# Sheet3.net
KiCad netlist of a schematic drawn in Altium Designer
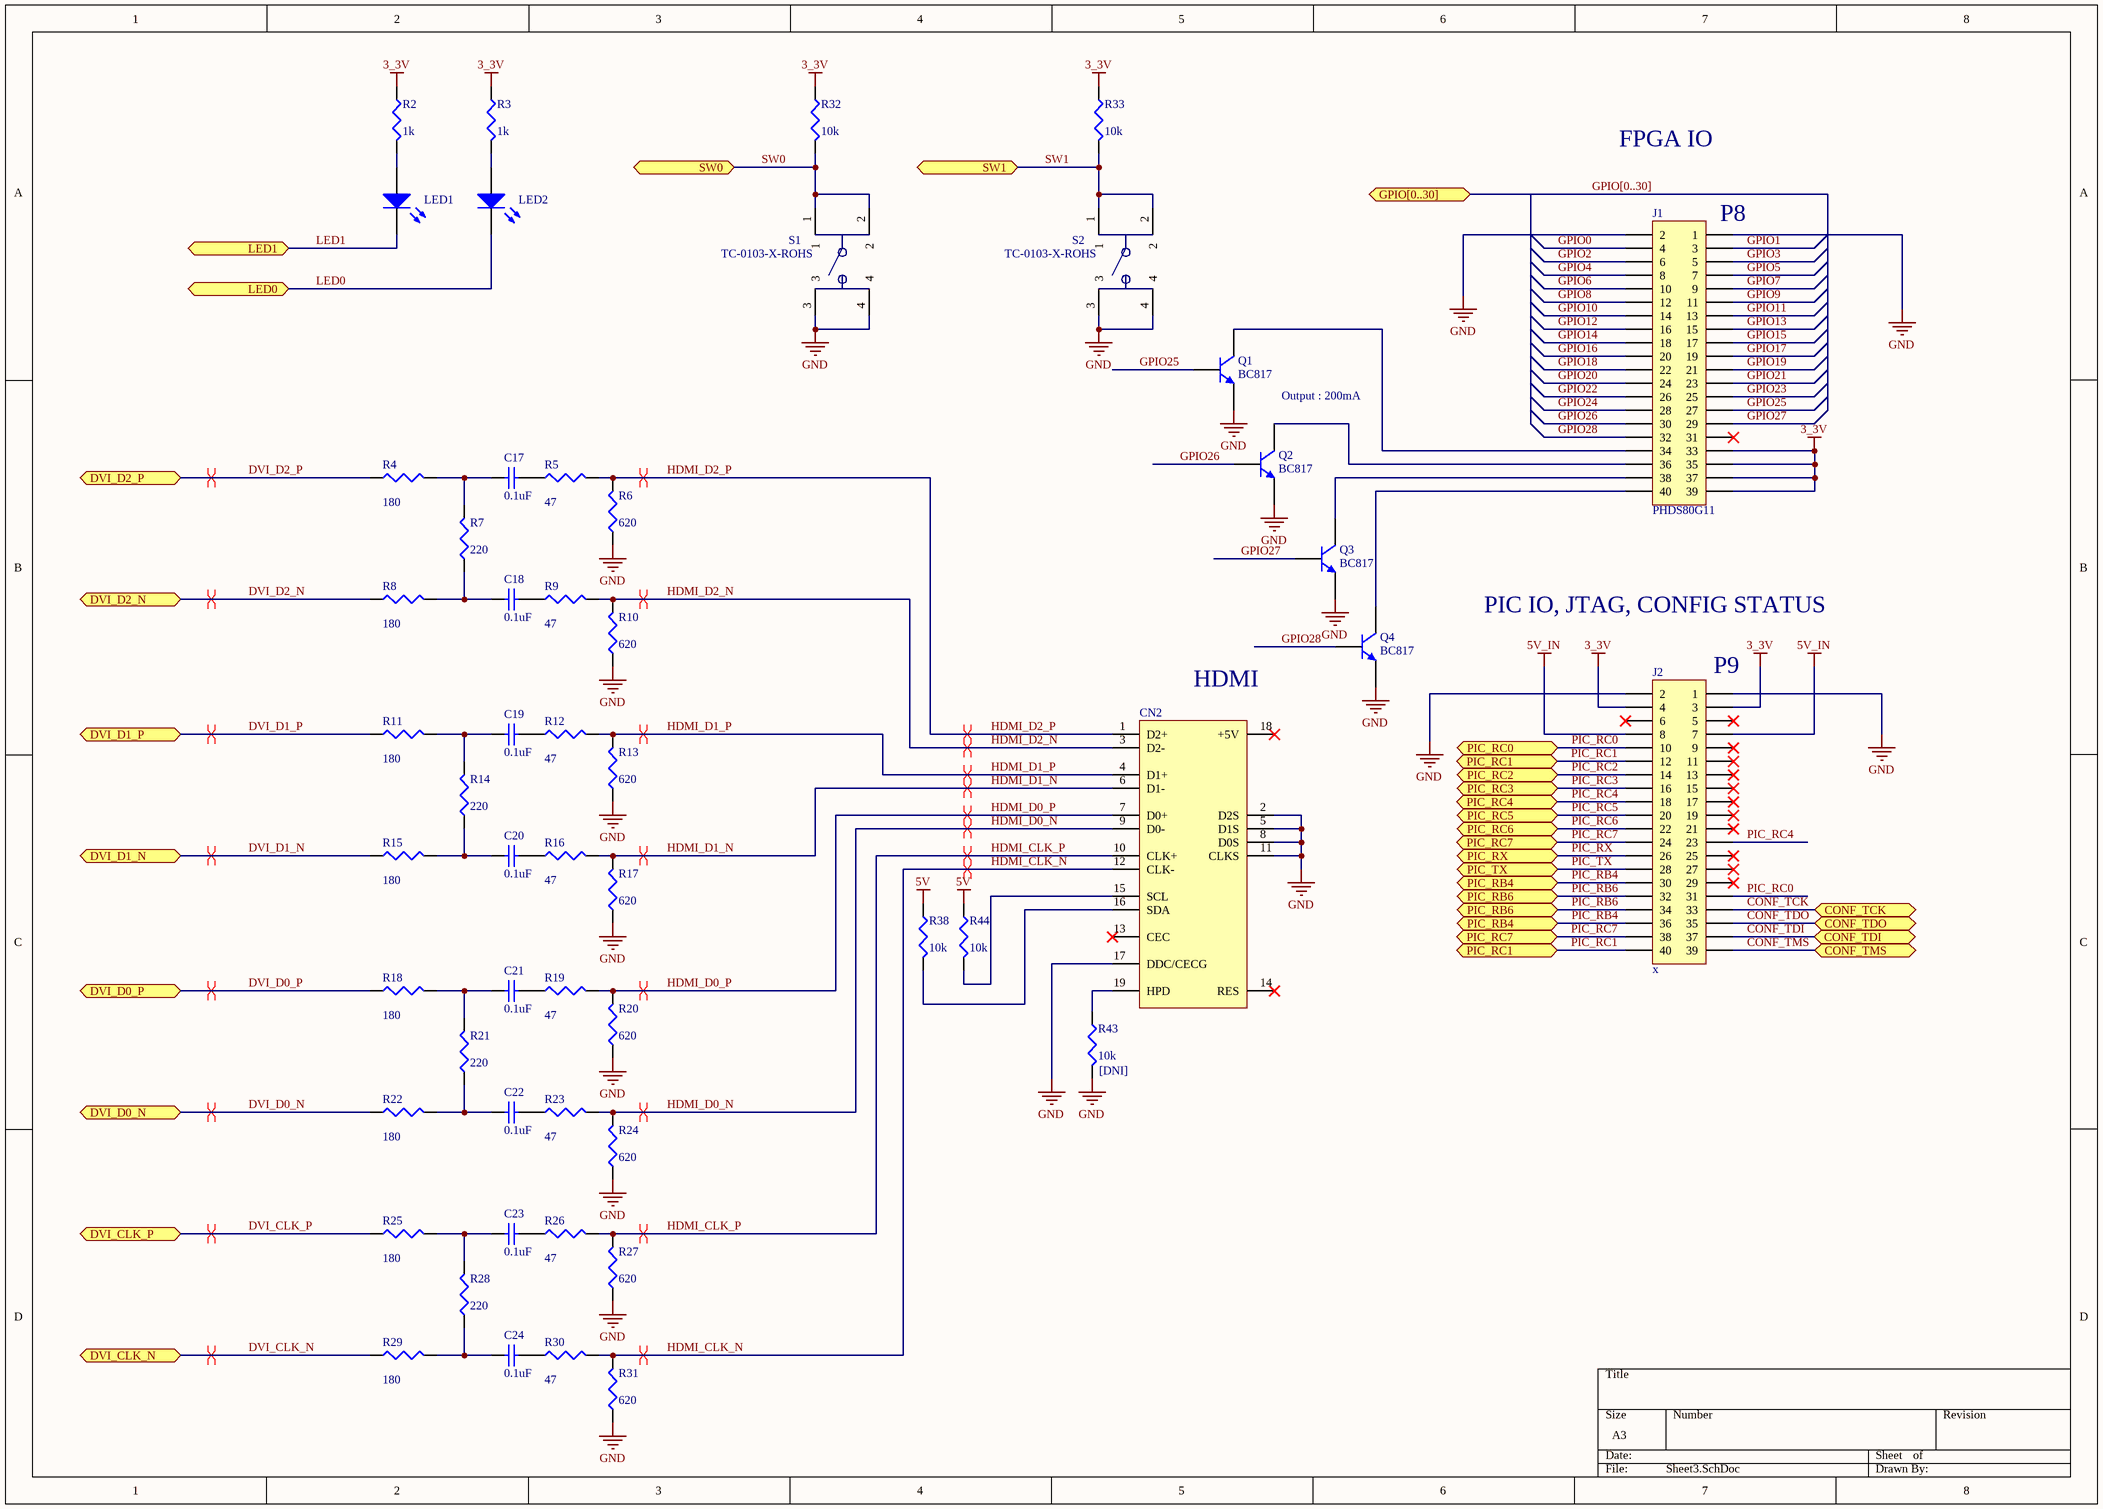
[diagram p0: Sheet3.SchDoc]

(export (version "E")
  (design (tool "Eeschema 10.0.6"))
  (components
    (comp (ref "C17")
      (value "0.1uF")
      (footprint "PcbLib:CHIP1608")
      (description "Capacitor (Semiconductor SIM Model)")
      (fields (field (name "Comment") "MCWR06X000 PTL") (field (name "PUBLISHER") "Altium Limited"))
      (libsource (lib "Miscellaneous Devices") (part "Cap Semi"))
    )
    (comp (ref "C18")
      (value "0.1uF")
      (footprint "PcbLib:CHIP1608")
      (description "Capacitor (Semiconductor SIM Model)")
      (fields (field (name "Comment") "MCWR06X000 PTL") (field (name "PUBLISHER") "Altium Limited"))
      (libsource (lib "Miscellaneous Devices") (part "Cap Semi"))
    )
    (comp (ref "C19")
      (value "0.1uF")
      (footprint "PcbLib:CHIP1608")
      (description "Capacitor (Semiconductor SIM Model)")
      (fields (field (name "Comment") "MCWR06X000 PTL") (field (name "PUBLISHER") "Altium Limited"))
      (libsource (lib "Miscellaneous Devices") (part "Cap Semi"))
    )
    (comp (ref "C20")
      (value "0.1uF")
      (footprint "PcbLib:CHIP1608")
      (description "Capacitor (Semiconductor SIM Model)")
      (fields (field (name "Comment") "MCWR06X000 PTL") (field (name "PUBLISHER") "Altium Limited"))
      (libsource (lib "Miscellaneous Devices") (part "Cap Semi"))
    )
    (comp (ref "C21")
      (value "0.1uF")
      (footprint "PcbLib:CHIP1608")
      (description "Capacitor (Semiconductor SIM Model)")
      (fields (field (name "Comment") "MCWR06X000 PTL") (field (name "PUBLISHER") "Altium Limited"))
      (libsource (lib "Miscellaneous Devices") (part "Cap Semi"))
    )
    (comp (ref "C22")
      (value "0.1uF")
      (footprint "PcbLib:CHIP1608")
      (description "Capacitor (Semiconductor SIM Model)")
      (fields (field (name "Comment") "MCWR06X000 PTL") (field (name "PUBLISHER") "Altium Limited"))
      (libsource (lib "Miscellaneous Devices") (part "Cap Semi"))
    )
    (comp (ref "C23")
      (value "0.1uF")
      (footprint "PcbLib:CHIP1608")
      (description "Capacitor (Semiconductor SIM Model)")
      (fields (field (name "Comment") "MCWR06X000 PTL") (field (name "PUBLISHER") "Altium Limited"))
      (libsource (lib "Miscellaneous Devices") (part "Cap Semi"))
    )
    (comp (ref "C24")
      (value "0.1uF")
      (footprint "PcbLib:CHIP1608")
      (description "Capacitor (Semiconductor SIM Model)")
      (fields (field (name "Comment") "MCWR06X000 PTL") (field (name "PUBLISHER") "Altium Limited"))
      (libsource (lib "Miscellaneous Devices") (part "Cap Semi"))
    )
    (comp (ref "CN2")
      (value "10029449-001RLF")
      (footprint "10029449-001RLF")
      (libsource (lib "Schlib") (part "HDMI_Connector"))
    )
    (comp (ref "J1")
      (value "PHDS80G11")
      (footprint "PcbLib:HDR2X20-Gemini")
      (description "Header, 20-Pin, Dual row")
      (fields (field (name "PUBLISHER") "Altium Limited"))
      (libsource (lib "Miscellaneous Connectors") (part "Header 20X2"))
    )
    (comp (ref "J2")
      (value "x")
      (footprint "PcbLib:HDR2X20-Gemini")
      (description "Header, 20-Pin, Dual row")
      (fields (field (name "PUBLISHER") "Altium Limited"))
      (libsource (lib "Miscellaneous Connectors") (part "Header 20X2"))
    )
    (comp (ref "LED1")
      (value "TO-3216BC-MAE")
      (footprint "PcbLib:LED3216")
      (description "OASISTEK (TO-3216BC-MAE)")
      (fields (field (name "PUBLISHER") "Altium Limited"))
      (libsource (lib "Miscellaneous Devices") (part "LED2"))
    )
    (comp (ref "LED2")
      (value "TO-3216BC-MAE")
      (footprint "PcbLib:LED3216")
      (description "OASISTEK (TO-3216BC-MAE)")
      (fields (field (name "PUBLISHER") "Altium Limited"))
      (libsource (lib "Miscellaneous Devices") (part "LED2"))
    )
    (comp (ref "Q1")
      (value "BC817")
      (footprint "PcbLib:SOT-23")
      (description "NPN General Purpose Amplifier")
      (fields (field (name "PUBLISHER") "Altium Limited"))
      (libsource (lib "Schlib") (part "BC817"))
    )
    (comp (ref "Q2")
      (value "BC817")
      (footprint "PcbLib:SOT-23")
      (description "NPN General Purpose Amplifier")
      (fields (field (name "PUBLISHER") "Altium Limited"))
      (libsource (lib "Schlib") (part "BC817"))
    )
    (comp (ref "Q3")
      (value "BC817")
      (footprint "PcbLib:SOT-23")
      (description "NPN General Purpose Amplifier")
      (fields (field (name "PUBLISHER") "Altium Limited"))
      (libsource (lib "Schlib") (part "BC817"))
    )
    (comp (ref "Q4")
      (value "BC817")
      (footprint "PcbLib:SOT-23")
      (description "NPN General Purpose Amplifier")
      (fields (field (name "PUBLISHER") "Altium Limited"))
      (libsource (lib "Schlib") (part "BC817"))
    )
    (comp (ref "R2")
      (value "1k")
      (footprint "PcbLib:CHIP1608")
      (description "Resistor")
      (fields (field (name "Comment") "MCMR06X1001FTL") (field (name "PUBLISHER") "Altium Limited"))
      (libsource (lib "Miscellaneous Devices") (part "Res3"))
    )
    (comp (ref "R3")
      (value "1k")
      (footprint "PcbLib:CHIP1608")
      (description "Resistor")
      (fields (field (name "Comment") "MCMR06X1001FTL") (field (name "PUBLISHER") "Altium Limited"))
      (libsource (lib "Miscellaneous Devices") (part "Res3"))
    )
    (comp (ref "R4")
      (value "180")
      (footprint "PcbLib:CHIP1608")
      (description "Resistor")
      (fields (field (name "Comment") "MC0063W06031270R") (field (name "PUBLISHER") "Altium Limited"))
      (libsource (lib "Miscellaneous Devices") (part "Res3"))
    )
    (comp (ref "R5")
      (value "47")
      (footprint "PcbLib:CHIP1608")
      (description "Resistor")
      (fields (field (name "Comment") "MCWR06X000 PTL") (field (name "PUBLISHER") "Altium Limited"))
      (libsource (lib "Miscellaneous Devices") (part "Res3"))
    )
    (comp (ref "R6")
      (value "620")
      (footprint "PcbLib:CHIP1608")
      (description "Resistor")
      (fields (field (name "Comment") "MCMR06X1001FTL") (field (name "PUBLISHER") "Altium Limited"))
      (libsource (lib "Miscellaneous Devices") (part "Res3"))
    )
    (comp (ref "R7")
      (value "220")
      (footprint "PcbLib:CHIP1608")
      (description "Resistor")
      (fields (field (name "Comment") "MCMR06X1001FTL") (field (name "PUBLISHER") "Altium Limited"))
      (libsource (lib "Miscellaneous Devices") (part "Res3"))
    )
    (comp (ref "R8")
      (value "180")
      (footprint "PcbLib:CHIP1608")
      (description "Resistor")
      (fields (field (name "Comment") "MC0063W06031270R") (field (name "PUBLISHER") "Altium Limited"))
      (libsource (lib "Miscellaneous Devices") (part "Res3"))
    )
    (comp (ref "R9")
      (value "47")
      (footprint "PcbLib:CHIP1608")
      (description "Resistor")
      (fields (field (name "Comment") "MCWR06X000 PTL") (field (name "PUBLISHER") "Altium Limited"))
      (libsource (lib "Miscellaneous Devices") (part "Res3"))
    )
    (comp (ref "R10")
      (value "620")
      (footprint "PcbLib:CHIP1608")
      (description "Resistor")
      (fields (field (name "Comment") "MCMR06X1001FTL") (field (name "PUBLISHER") "Altium Limited"))
      (libsource (lib "Miscellaneous Devices") (part "Res3"))
    )
    (comp (ref "R11")
      (value "180")
      (footprint "PcbLib:CHIP1608")
      (description "Resistor")
      (fields (field (name "Comment") "MC0063W06031270R") (field (name "PUBLISHER") "Altium Limited"))
      (libsource (lib "Miscellaneous Devices") (part "Res3"))
    )
    (comp (ref "R12")
      (value "47")
      (footprint "PcbLib:CHIP1608")
      (description "Resistor")
      (fields (field (name "Comment") "MCWR06X000 PTL") (field (name "PUBLISHER") "Altium Limited"))
      (libsource (lib "Miscellaneous Devices") (part "Res3"))
    )
    (comp (ref "R13")
      (value "620")
      (footprint "PcbLib:CHIP1608")
      (description "Resistor")
      (fields (field (name "Comment") "MCMR06X1001FTL") (field (name "PUBLISHER") "Altium Limited"))
      (libsource (lib "Miscellaneous Devices") (part "Res3"))
    )
    (comp (ref "R14")
      (value "220")
      (footprint "PcbLib:CHIP1608")
      (description "Resistor")
      (fields (field (name "Comment") "MCMR06X1001FTL") (field (name "PUBLISHER") "Altium Limited"))
      (libsource (lib "Miscellaneous Devices") (part "Res3"))
    )
    (comp (ref "R15")
      (value "180")
      (footprint "PcbLib:CHIP1608")
      (description "Resistor")
      (fields (field (name "Comment") "MC0063W06031270R") (field (name "PUBLISHER") "Altium Limited"))
      (libsource (lib "Miscellaneous Devices") (part "Res3"))
    )
    (comp (ref "R16")
      (value "47")
      (footprint "PcbLib:CHIP1608")
      (description "Resistor")
      (fields (field (name "Comment") "MCWR06X000 PTL") (field (name "PUBLISHER") "Altium Limited"))
      (libsource (lib "Miscellaneous Devices") (part "Res3"))
    )
    (comp (ref "R17")
      (value "620")
      (footprint "PcbLib:CHIP1608")
      (description "Resistor")
      (fields (field (name "Comment") "MCMR06X1001FTL") (field (name "PUBLISHER") "Altium Limited"))
      (libsource (lib "Miscellaneous Devices") (part "Res3"))
    )
    (comp (ref "R18")
      (value "180")
      (footprint "PcbLib:CHIP1608")
      (description "Resistor")
      (fields (field (name "Comment") "MC0063W06031270R") (field (name "PUBLISHER") "Altium Limited"))
      (libsource (lib "Miscellaneous Devices") (part "Res3"))
    )
    (comp (ref "R19")
      (value "47")
      (footprint "PcbLib:CHIP1608")
      (description "Resistor")
      (fields (field (name "Comment") "MCWR06X000 PTL") (field (name "PUBLISHER") "Altium Limited"))
      (libsource (lib "Miscellaneous Devices") (part "Res3"))
    )
    (comp (ref "R20")
      (value "620")
      (footprint "PcbLib:CHIP1608")
      (description "Resistor")
      (fields (field (name "Comment") "MCMR06X1001FTL") (field (name "PUBLISHER") "Altium Limited"))
      (libsource (lib "Miscellaneous Devices") (part "Res3"))
    )
    (comp (ref "R21")
      (value "220")
      (footprint "PcbLib:CHIP1608")
      (description "Resistor")
      (fields (field (name "Comment") "MCMR06X1001FTL") (field (name "PUBLISHER") "Altium Limited"))
      (libsource (lib "Miscellaneous Devices") (part "Res3"))
    )
    (comp (ref "R22")
      (value "180")
      (footprint "PcbLib:CHIP1608")
      (description "Resistor")
      (fields (field (name "Comment") "MC0063W06031270R") (field (name "PUBLISHER") "Altium Limited"))
      (libsource (lib "Miscellaneous Devices") (part "Res3"))
    )
    (comp (ref "R23")
      (value "47")
      (footprint "PcbLib:CHIP1608")
      (description "Resistor")
      (fields (field (name "Comment") "MCWR06X000 PTL") (field (name "PUBLISHER") "Altium Limited"))
      (libsource (lib "Miscellaneous Devices") (part "Res3"))
    )
    (comp (ref "R24")
      (value "620")
      (footprint "PcbLib:CHIP1608")
      (description "Resistor")
      (fields (field (name "Comment") "MCMR06X1001FTL") (field (name "PUBLISHER") "Altium Limited"))
      (libsource (lib "Miscellaneous Devices") (part "Res3"))
    )
    (comp (ref "R25")
      (value "180")
      (footprint "PcbLib:CHIP1608")
      (description "Resistor")
      (fields (field (name "Comment") "MC0063W06031270R") (field (name "PUBLISHER") "Altium Limited"))
      (libsource (lib "Miscellaneous Devices") (part "Res3"))
    )
    (comp (ref "R26")
      (value "47")
      (footprint "PcbLib:CHIP1608")
      (description "Resistor")
      (fields (field (name "Comment") "MCWR06X000 PTL") (field (name "PUBLISHER") "Altium Limited"))
      (libsource (lib "Miscellaneous Devices") (part "Res3"))
    )
    (comp (ref "R27")
      (value "620")
      (footprint "PcbLib:CHIP1608")
      (description "Resistor")
      (fields (field (name "Comment") "MCMR06X1001FTL") (field (name "PUBLISHER") "Altium Limited"))
      (libsource (lib "Miscellaneous Devices") (part "Res3"))
    )
    (comp (ref "R28")
      (value "220")
      (footprint "PcbLib:CHIP1608")
      (description "Resistor")
      (fields (field (name "Comment") "MCMR06X1001FTL") (field (name "PUBLISHER") "Altium Limited"))
      (libsource (lib "Miscellaneous Devices") (part "Res3"))
    )
    (comp (ref "R29")
      (value "180")
      (footprint "PcbLib:CHIP1608")
      (description "Resistor")
      (fields (field (name "Comment") "MC0063W06031270R") (field (name "PUBLISHER") "Altium Limited"))
      (libsource (lib "Miscellaneous Devices") (part "Res3"))
    )
    (comp (ref "R30")
      (value "47")
      (footprint "PcbLib:CHIP1608")
      (description "Resistor")
      (fields (field (name "Comment") "MCWR06X000 PTL") (field (name "PUBLISHER") "Altium Limited"))
      (libsource (lib "Miscellaneous Devices") (part "Res3"))
    )
    (comp (ref "R31")
      (value "620")
      (footprint "PcbLib:CHIP1608")
      (description "Resistor")
      (fields (field (name "Comment") "MCMR06X1001FTL") (field (name "PUBLISHER") "Altium Limited"))
      (libsource (lib "Miscellaneous Devices") (part "Res3"))
    )
    (comp (ref "R32")
      (value "10k")
      (footprint "PcbLib:CHIP1608")
      (description "Resistor")
      (fields (field (name "Comment") "MCWR06X1002FTL") (field (name "PUBLISHER") "Altium Limited"))
      (libsource (lib "Miscellaneous Devices") (part "Res3"))
    )
    (comp (ref "R33")
      (value "10k")
      (footprint "PcbLib:CHIP1608")
      (description "Resistor")
      (fields (field (name "Comment") "MCWR06X1002FTL") (field (name "PUBLISHER") "Altium Limited"))
      (libsource (lib "Miscellaneous Devices") (part "Res3"))
    )
    (comp (ref "R38")
      (value "10k")
      (footprint "PcbLib:CHIP1608")
      (description "Resistor")
      (fields (field (name "Comment") "MCWR06X1002FTL") (field (name "PUBLISHER") "Altium Limited"))
      (libsource (lib "Miscellaneous Devices") (part "Res3"))
    )
    (comp (ref "R43")
      (value "10k")
      (footprint "PcbLib:CHIP1608")
      (description "Resistor")
      (fields
        (field (name "ASSEMBLY") "[DNI]")
        (field (name "Comment") "MCWR06X1002FTL")
        (field (name "PUBLISHER") "Altium Limited")
      )
      (libsource (lib "Miscellaneous Devices") (part "Res3"))
    )
    (comp (ref "R44")
      (value "10k")
      (footprint "PcbLib:CHIP1608")
      (description "Resistor")
      (fields (field (name "Comment") "MCWR06X1002FTL") (field (name "PUBLISHER") "Altium Limited"))
      (libsource (lib "Miscellaneous Devices") (part "Res3"))
    )
    (comp (ref "S1")
      (value "TC-0103-X-ROHS")
      (footprint "TACK_SW 6x6mm")
      (description "WEALTH METAL")
      (libsource (lib "Schlib1") (part "TC-0103-X-ROHS"))
    )
    (comp (ref "S2")
      (value "TC-0103-X-ROHS")
      (footprint "TACK_SW 6x6mm")
      (description "WEALTH METAL")
      (libsource (lib "Schlib1") (part "TC-0103-X-ROHS"))
    )
  )
  (nets
    (net (code "3") (name "/CONF_TCK") (class "Default")
      (node (ref "J2") (pin "33") (pinfunction "33_33") (pintype "passive"))
    )
    (net (code "4") (name "/CONF_TDI") (class "Default")
      (node (ref "J2") (pin "37") (pinfunction "37_37") (pintype "passive"))
    )
    (net (code "5") (name "/CONF_TDO") (class "Default")
      (node (ref "J2") (pin "35") (pinfunction "35_35") (pintype "passive"))
    )
    (net (code "6") (name "/CONF_TMS") (class "Default")
      (node (ref "J2") (pin "39") (pinfunction "39_39") (pintype "passive"))
    )
    (net (code "7") (name "/DVI_CLK_N") (class "Default")
      (node (ref "R29") (pin "1") (pinfunction "1_1") (pintype "passive"))
    )
    (net (code "8") (name "/DVI_CLK_P") (class "Default")
      (node (ref "R25") (pin "1") (pinfunction "1_1") (pintype "passive"))
    )
    (net (code "9") (name "/DVI_D0_N") (class "Default")
      (node (ref "R22") (pin "1") (pinfunction "1_1") (pintype "passive"))
    )
    (net (code "10") (name "/DVI_D0_P") (class "Default")
      (node (ref "R18") (pin "1") (pinfunction "1_1") (pintype "passive"))
    )
    (net (code "11") (name "/DVI_D1_N") (class "Default")
      (node (ref "R15") (pin "1") (pinfunction "1_1") (pintype "passive"))
    )
    (net (code "12") (name "/DVI_D1_P") (class "Default")
      (node (ref "R11") (pin "1") (pinfunction "1_1") (pintype "passive"))
    )
    (net (code "13") (name "/DVI_D2_N") (class "Default")
      (node (ref "R8") (pin "1") (pinfunction "1_1") (pintype "passive"))
    )
    (net (code "14") (name "/DVI_D2_P") (class "Default")
      (node (ref "R4") (pin "1") (pinfunction "1_1") (pintype "passive"))
    )
    (net (code "15") (name "/GPIO0") (class "Default")
      (node (ref "J1") (pin "4") (pinfunction "4_4") (pintype "passive"))
    )
    (net (code "16") (name "/GPIO1") (class "Default")
      (node (ref "J1") (pin "3") (pinfunction "3_3") (pintype "passive"))
    )
    (net (code "17") (name "/GPIO2") (class "Default")
      (node (ref "J1") (pin "6") (pinfunction "6_6") (pintype "passive"))
    )
    (net (code "18") (name "/GPIO3") (class "Default")
      (node (ref "J1") (pin "5") (pinfunction "5_5") (pintype "passive"))
    )
    (net (code "19") (name "/GPIO4") (class "Default")
      (node (ref "J1") (pin "8") (pinfunction "8_8") (pintype "passive"))
    )
    (net (code "20") (name "/GPIO5") (class "Default")
      (node (ref "J1") (pin "7") (pinfunction "7_7") (pintype "passive"))
    )
    (net (code "21") (name "/GPIO6") (class "Default")
      (node (ref "J1") (pin "10") (pinfunction "10_10") (pintype "passive"))
    )
    (net (code "22") (name "/GPIO7") (class "Default")
      (node (ref "J1") (pin "9") (pinfunction "9_9") (pintype "passive"))
    )
    (net (code "23") (name "/GPIO8") (class "Default")
      (node (ref "J1") (pin "12") (pinfunction "12_12") (pintype "passive"))
    )
    (net (code "24") (name "/GPIO9") (class "Default")
      (node (ref "J1") (pin "11") (pinfunction "11_11") (pintype "passive"))
    )
    (net (code "25") (name "/GPIO10") (class "Default")
      (node (ref "J1") (pin "14") (pinfunction "14_14") (pintype "passive"))
    )
    (net (code "26") (name "/GPIO11") (class "Default")
      (node (ref "J1") (pin "13") (pinfunction "13_13") (pintype "passive"))
    )
    (net (code "27") (name "/GPIO12") (class "Default")
      (node (ref "J1") (pin "16") (pinfunction "16_16") (pintype "passive"))
    )
    (net (code "28") (name "/GPIO13") (class "Default")
      (node (ref "J1") (pin "15") (pinfunction "15_15") (pintype "passive"))
    )
    (net (code "29") (name "/GPIO14") (class "Default")
      (node (ref "J1") (pin "18") (pinfunction "18_18") (pintype "passive"))
    )
    (net (code "30") (name "/GPIO15") (class "Default")
      (node (ref "J1") (pin "17") (pinfunction "17_17") (pintype "passive"))
    )
    (net (code "31") (name "/GPIO16") (class "Default")
      (node (ref "J1") (pin "20") (pinfunction "20_20") (pintype "passive"))
    )
    (net (code "32") (name "/GPIO17") (class "Default")
      (node (ref "J1") (pin "19") (pinfunction "19_19") (pintype "passive"))
    )
    (net (code "33") (name "/GPIO18") (class "Default")
      (node (ref "J1") (pin "22") (pinfunction "22_22") (pintype "passive"))
    )
    (net (code "34") (name "/GPIO19") (class "Default")
      (node (ref "J1") (pin "21") (pinfunction "21_21") (pintype "passive"))
    )
    (net (code "35") (name "/GPIO20") (class "Default")
      (node (ref "J1") (pin "24") (pinfunction "24_24") (pintype "passive"))
    )
    (net (code "36") (name "/GPIO21") (class "Default")
      (node (ref "J1") (pin "23") (pinfunction "23_23") (pintype "passive"))
    )
    (net (code "37") (name "/GPIO22") (class "Default")
      (node (ref "J1") (pin "26") (pinfunction "26_26") (pintype "passive"))
    )
    (net (code "38") (name "/GPIO23") (class "Default")
      (node (ref "J1") (pin "25") (pinfunction "25_25") (pintype "passive"))
    )
    (net (code "39") (name "/GPIO24") (class "Default")
      (node (ref "J1") (pin "28") (pinfunction "28_28") (pintype "passive"))
    )
    (net (code "40") (name "/GPIO25") (class "Default")
      (node (ref "J1") (pin "27") (pinfunction "27_27") (pintype "passive"))
      (node (ref "Q1") (pin "1") (pinfunction "B_1") (pintype "passive"))
    )
    (net (code "41") (name "/GPIO26") (class "Default")
      (node (ref "J1") (pin "30") (pinfunction "30_30") (pintype "passive"))
      (node (ref "Q2") (pin "1") (pinfunction "B_1") (pintype "passive"))
    )
    (net (code "42") (name "/GPIO27") (class "Default")
      (node (ref "J1") (pin "29") (pinfunction "29_29") (pintype "passive"))
      (node (ref "Q3") (pin "1") (pinfunction "B_1") (pintype "passive"))
    )
    (net (code "43") (name "/GPIO28") (class "Default")
      (node (ref "J1") (pin "32") (pinfunction "32_32") (pintype "passive"))
      (node (ref "Q4") (pin "1") (pinfunction "B_1") (pintype "passive"))
    )
    (net (code "45") (name "/HDMI_CLK_N") (class "Default")
      (node (ref "CN2") (pin "12") (pinfunction "CLK-_12") (pintype "passive"))
      (node (ref "R30") (pin "2") (pinfunction "2_2") (pintype "passive"))
      (node (ref "R31") (pin "2") (pinfunction "2_2") (pintype "passive"))
    )
    (net (code "46") (name "/HDMI_CLK_P") (class "Default")
      (node (ref "CN2") (pin "10") (pinfunction "CLK+_10") (pintype "passive"))
      (node (ref "R26") (pin "2") (pinfunction "2_2") (pintype "passive"))
      (node (ref "R27") (pin "2") (pinfunction "2_2") (pintype "passive"))
    )
    (net (code "47") (name "/HDMI_D0_N") (class "Default")
      (node (ref "CN2") (pin "9") (pinfunction "D0-_9") (pintype "passive"))
      (node (ref "R23") (pin "2") (pinfunction "2_2") (pintype "passive"))
      (node (ref "R24") (pin "2") (pinfunction "2_2") (pintype "passive"))
    )
    (net (code "48") (name "/HDMI_D0_P") (class "Default")
      (node (ref "CN2") (pin "7") (pinfunction "D0+_7") (pintype "passive"))
      (node (ref "R19") (pin "2") (pinfunction "2_2") (pintype "passive"))
      (node (ref "R20") (pin "2") (pinfunction "2_2") (pintype "passive"))
    )
    (net (code "49") (name "/HDMI_D1_N") (class "Default")
      (node (ref "CN2") (pin "6") (pinfunction "D1-_6") (pintype "passive"))
      (node (ref "R16") (pin "2") (pinfunction "2_2") (pintype "passive"))
      (node (ref "R17") (pin "2") (pinfunction "2_2") (pintype "passive"))
    )
    (net (code "50") (name "/HDMI_D1_P") (class "Default")
      (node (ref "CN2") (pin "4") (pinfunction "D1+_4") (pintype "passive"))
      (node (ref "R12") (pin "2") (pinfunction "2_2") (pintype "passive"))
      (node (ref "R13") (pin "2") (pinfunction "2_2") (pintype "passive"))
    )
    (net (code "51") (name "/HDMI_D2_N") (class "Default")
      (node (ref "CN2") (pin "3") (pinfunction "D2-_3") (pintype "passive"))
      (node (ref "R10") (pin "2") (pinfunction "2_2") (pintype "passive"))
      (node (ref "R9") (pin "2") (pinfunction "2_2") (pintype "passive"))
    )
    (net (code "52") (name "/HDMI_D2_P") (class "Default")
      (node (ref "CN2") (pin "1") (pinfunction "D2+_1") (pintype "passive"))
      (node (ref "R5") (pin "2") (pinfunction "2_2") (pintype "passive"))
      (node (ref "R6") (pin "2") (pinfunction "2_2") (pintype "passive"))
    )
    (net (code "53") (name "/LED0") (class "Default")
      (node (ref "LED2") (pin "2") (pinfunction "K_2") (pintype "passive"))
    )
    (net (code "54") (name "/LED1") (class "Default")
      (node (ref "LED1") (pin "2") (pinfunction "K_2") (pintype "passive"))
    )
    (net (code "55") (name "/PIC_RB4") (class "Default")
      (node (ref "J2") (pin "30") (pinfunction "30_30") (pintype "passive"))
      (node (ref "J2") (pin "36") (pinfunction "36_36") (pintype "passive"))
    )
    (net (code "56") (name "/PIC_RB6") (class "Default")
      (node (ref "J2") (pin "32") (pinfunction "32_32") (pintype "passive"))
      (node (ref "J2") (pin "34") (pinfunction "34_34") (pintype "passive"))
    )
    (net (code "57") (name "/PIC_RC0") (class "Default")
      (node (ref "J2") (pin "10") (pinfunction "10_10") (pintype "passive"))
      (node (ref "J2") (pin "31") (pinfunction "31_31") (pintype "passive"))
    )
    (net (code "58") (name "/PIC_RC1") (class "Default")
      (node (ref "J2") (pin "12") (pinfunction "12_12") (pintype "passive"))
      (node (ref "J2") (pin "40") (pinfunction "40_40") (pintype "passive"))
    )
    (net (code "59") (name "/PIC_RC2") (class "Default")
      (node (ref "J2") (pin "14") (pinfunction "14_14") (pintype "passive"))
    )
    (net (code "60") (name "/PIC_RC3") (class "Default")
      (node (ref "J2") (pin "16") (pinfunction "16_16") (pintype "passive"))
    )
    (net (code "61") (name "/PIC_RC4") (class "Default")
      (node (ref "J2") (pin "18") (pinfunction "18_18") (pintype "passive"))
      (node (ref "J2") (pin "23") (pinfunction "23_23") (pintype "passive"))
    )
    (net (code "62") (name "/PIC_RC5") (class "Default")
      (node (ref "J2") (pin "20") (pinfunction "20_20") (pintype "passive"))
    )
    (net (code "63") (name "/PIC_RC6") (class "Default")
      (node (ref "J2") (pin "22") (pinfunction "22_22") (pintype "passive"))
    )
    (net (code "64") (name "/PIC_RC7") (class "Default")
      (node (ref "J2") (pin "24") (pinfunction "24_24") (pintype "passive"))
      (node (ref "J2") (pin "38") (pinfunction "38_38") (pintype "passive"))
    )
    (net (code "65") (name "/PIC_RX") (class "Default")
      (node (ref "J2") (pin "26") (pinfunction "26_26") (pintype "passive"))
    )
    (net (code "66") (name "/PIC_TX") (class "Default")
      (node (ref "J2") (pin "28") (pinfunction "28_28") (pintype "passive"))
    )
    (net (code "67") (name "/SW0") (class "Default")
      (node (ref "R32") (pin "2") (pinfunction "2_2") (pintype "passive"))
      (node (ref "S1") (pin "1") (pinfunction "1_1") (pintype "passive"))
      (node (ref "S1") (pin "2") (pinfunction "2_2") (pintype "passive"))
    )
    (net (code "68") (name "/SW1") (class "Default")
      (node (ref "R33") (pin "2") (pinfunction "2_2") (pintype "passive"))
      (node (ref "S2") (pin "1") (pinfunction "1_1") (pintype "passive"))
      (node (ref "S2") (pin "2") (pinfunction "2_2") (pintype "passive"))
    )
    (net (code "69") (name "3_3V") (class "Default")
      (node (ref "J1") (pin "33") (pinfunction "33_33") (pintype "passive"))
      (node (ref "J1") (pin "35") (pinfunction "35_35") (pintype "passive"))
      (node (ref "J1") (pin "37") (pinfunction "37_37") (pintype "passive"))
      (node (ref "J1") (pin "39") (pinfunction "39_39") (pintype "passive"))
      (node (ref "J2") (pin "3") (pinfunction "3_3") (pintype "passive"))
      (node (ref "J2") (pin "4") (pinfunction "4_4") (pintype "passive"))
      (node (ref "R2") (pin "1") (pinfunction "1_1") (pintype "passive"))
      (node (ref "R3") (pin "1") (pinfunction "1_1") (pintype "passive"))
      (node (ref "R32") (pin "1") (pinfunction "1_1") (pintype "passive"))
      (node (ref "R33") (pin "1") (pinfunction "1_1") (pintype "passive"))
    )
    (net (code "70") (name "5V") (class "Default")
      (node (ref "R38") (pin "1") (pinfunction "1_1") (pintype "passive"))
      (node (ref "R44") (pin "1") (pinfunction "1_1") (pintype "passive"))
    )
    (net (code "71") (name "5V_IN") (class "Default")
      (node (ref "J2") (pin "7") (pinfunction "7_7") (pintype "passive"))
      (node (ref "J2") (pin "8") (pinfunction "8_8") (pintype "passive"))
    )
    (net (code "72") (name "GND") (class "Default")
      (node (ref "CN2") (pin "11") (pinfunction "CLKS_11") (pintype "passive"))
      (node (ref "CN2") (pin "17") (pinfunction "DDC/CECG_17") (pintype "passive"))
      (node (ref "CN2") (pin "2") (pinfunction "D2S_2") (pintype "passive"))
      (node (ref "CN2") (pin "5") (pinfunction "D1S_5") (pintype "passive"))
      (node (ref "CN2") (pin "8") (pinfunction "D0S_8") (pintype "passive"))
      (node (ref "J1") (pin "1") (pinfunction "1_1") (pintype "passive"))
      (node (ref "J1") (pin "2") (pinfunction "2_2") (pintype "passive"))
      (node (ref "J2") (pin "1") (pinfunction "1_1") (pintype "passive"))
      (node (ref "J2") (pin "2") (pinfunction "2_2") (pintype "passive"))
      (node (ref "Q1") (pin "2") (pinfunction "E_2") (pintype "passive"))
      (node (ref "Q2") (pin "2") (pinfunction "E_2") (pintype "passive"))
      (node (ref "Q3") (pin "2") (pinfunction "E_2") (pintype "passive"))
      (node (ref "Q4") (pin "2") (pinfunction "E_2") (pintype "passive"))
      (node (ref "R10") (pin "1") (pinfunction "1_1") (pintype "passive"))
      (node (ref "R13") (pin "1") (pinfunction "1_1") (pintype "passive"))
      (node (ref "R17") (pin "1") (pinfunction "1_1") (pintype "passive"))
      (node (ref "R20") (pin "1") (pinfunction "1_1") (pintype "passive"))
      (node (ref "R24") (pin "1") (pinfunction "1_1") (pintype "passive"))
      (node (ref "R27") (pin "1") (pinfunction "1_1") (pintype "passive"))
      (node (ref "R31") (pin "1") (pinfunction "1_1") (pintype "passive"))
      (node (ref "R43") (pin "2") (pinfunction "2_2") (pintype "passive"))
      (node (ref "R6") (pin "1") (pinfunction "1_1") (pintype "passive"))
      (node (ref "S1") (pin "3") (pinfunction "3_3") (pintype "passive"))
      (node (ref "S1") (pin "4") (pinfunction "4_4") (pintype "passive"))
      (node (ref "S2") (pin "3") (pinfunction "3_3") (pintype "passive"))
      (node (ref "S2") (pin "4") (pinfunction "4_4") (pintype "passive"))
    )
    (net (code "73") (name "Net-(C17-Pad1)") (class "Default")
      (node (ref "C17") (pin "1") (pinfunction "1_1") (pintype "passive"))
      (node (ref "R5") (pin "1") (pinfunction "1_1") (pintype "passive"))
    )
    (net (code "74") (name "Net-(C17-Pad2)") (class "Default")
      (node (ref "C17") (pin "2") (pinfunction "2_2") (pintype "passive"))
      (node (ref "R4") (pin "2") (pinfunction "2_2") (pintype "passive"))
      (node (ref "R7") (pin "2") (pinfunction "2_2") (pintype "passive"))
    )
    (net (code "75") (name "Net-(C18-Pad1)") (class "Default")
      (node (ref "C18") (pin "1") (pinfunction "1_1") (pintype "passive"))
      (node (ref "R9") (pin "1") (pinfunction "1_1") (pintype "passive"))
    )
    (net (code "76") (name "Net-(C18-Pad2)") (class "Default")
      (node (ref "C18") (pin "2") (pinfunction "2_2") (pintype "passive"))
      (node (ref "R7") (pin "1") (pinfunction "1_1") (pintype "passive"))
      (node (ref "R8") (pin "2") (pinfunction "2_2") (pintype "passive"))
    )
    (net (code "77") (name "Net-(C19-Pad1)") (class "Default")
      (node (ref "C19") (pin "1") (pinfunction "1_1") (pintype "passive"))
      (node (ref "R12") (pin "1") (pinfunction "1_1") (pintype "passive"))
    )
    (net (code "78") (name "Net-(C19-Pad2)") (class "Default")
      (node (ref "C19") (pin "2") (pinfunction "2_2") (pintype "passive"))
      (node (ref "R11") (pin "2") (pinfunction "2_2") (pintype "passive"))
      (node (ref "R14") (pin "2") (pinfunction "2_2") (pintype "passive"))
    )
    (net (code "79") (name "Net-(C20-Pad1)") (class "Default")
      (node (ref "C20") (pin "1") (pinfunction "1_1") (pintype "passive"))
      (node (ref "R16") (pin "1") (pinfunction "1_1") (pintype "passive"))
    )
    (net (code "80") (name "Net-(C20-Pad2)") (class "Default")
      (node (ref "C20") (pin "2") (pinfunction "2_2") (pintype "passive"))
      (node (ref "R14") (pin "1") (pinfunction "1_1") (pintype "passive"))
      (node (ref "R15") (pin "2") (pinfunction "2_2") (pintype "passive"))
    )
    (net (code "81") (name "Net-(C21-Pad1)") (class "Default")
      (node (ref "C21") (pin "1") (pinfunction "1_1") (pintype "passive"))
      (node (ref "R19") (pin "1") (pinfunction "1_1") (pintype "passive"))
    )
    (net (code "82") (name "Net-(C21-Pad2)") (class "Default")
      (node (ref "C21") (pin "2") (pinfunction "2_2") (pintype "passive"))
      (node (ref "R18") (pin "2") (pinfunction "2_2") (pintype "passive"))
      (node (ref "R21") (pin "2") (pinfunction "2_2") (pintype "passive"))
    )
    (net (code "83") (name "Net-(C22-Pad1)") (class "Default")
      (node (ref "C22") (pin "1") (pinfunction "1_1") (pintype "passive"))
      (node (ref "R23") (pin "1") (pinfunction "1_1") (pintype "passive"))
    )
    (net (code "84") (name "Net-(C22-Pad2)") (class "Default")
      (node (ref "C22") (pin "2") (pinfunction "2_2") (pintype "passive"))
      (node (ref "R21") (pin "1") (pinfunction "1_1") (pintype "passive"))
      (node (ref "R22") (pin "2") (pinfunction "2_2") (pintype "passive"))
    )
    (net (code "85") (name "Net-(C23-Pad1)") (class "Default")
      (node (ref "C23") (pin "1") (pinfunction "1_1") (pintype "passive"))
      (node (ref "R26") (pin "1") (pinfunction "1_1") (pintype "passive"))
    )
    (net (code "86") (name "Net-(C23-Pad2)") (class "Default")
      (node (ref "C23") (pin "2") (pinfunction "2_2") (pintype "passive"))
      (node (ref "R25") (pin "2") (pinfunction "2_2") (pintype "passive"))
      (node (ref "R28") (pin "2") (pinfunction "2_2") (pintype "passive"))
    )
    (net (code "87") (name "Net-(C24-Pad1)") (class "Default")
      (node (ref "C24") (pin "1") (pinfunction "1_1") (pintype "passive"))
      (node (ref "R30") (pin "1") (pinfunction "1_1") (pintype "passive"))
    )
    (net (code "88") (name "Net-(C24-Pad2)") (class "Default")
      (node (ref "C24") (pin "2") (pinfunction "2_2") (pintype "passive"))
      (node (ref "R28") (pin "1") (pinfunction "1_1") (pintype "passive"))
      (node (ref "R29") (pin "2") (pinfunction "2_2") (pintype "passive"))
    )
    (net (code "89") (name "Net-(CN2-HPD)") (class "Default")
      (node (ref "CN2") (pin "19") (pinfunction "HPD_19") (pintype "passive"))
      (node (ref "R43") (pin "1") (pinfunction "1_1") (pintype "passive"))
    )
    (net (code "90") (name "Net-(CN2-SCL)") (class "Default")
      (node (ref "CN2") (pin "15") (pinfunction "SCL_15") (pintype "passive"))
      (node (ref "R44") (pin "2") (pinfunction "2_2") (pintype "passive"))
    )
    (net (code "91") (name "Net-(CN2-SDA)") (class "Default")
      (node (ref "CN2") (pin "16") (pinfunction "SDA_16") (pintype "passive"))
      (node (ref "R38") (pin "2") (pinfunction "2_2") (pintype "passive"))
    )
    (net (code "92") (name "Net-(LED1-A)") (class "Default")
      (node (ref "LED1") (pin "1") (pinfunction "A_1") (pintype "passive"))
      (node (ref "R2") (pin "2") (pinfunction "2_2") (pintype "passive"))
    )
    (net (code "93") (name "Net-(LED2-A)") (class "Default")
      (node (ref "LED2") (pin "1") (pinfunction "A_1") (pintype "passive"))
      (node (ref "R3") (pin "2") (pinfunction "2_2") (pintype "passive"))
    )
    (net (code "94") (name "Net-(Q1-C)") (class "Default")
      (node (ref "J1") (pin "34") (pinfunction "34_34") (pintype "passive"))
      (node (ref "Q1") (pin "3") (pinfunction "C_3") (pintype "passive"))
    )
    (net (code "95") (name "Net-(Q2-C)") (class "Default")
      (node (ref "J1") (pin "36") (pinfunction "36_36") (pintype "passive"))
      (node (ref "Q2") (pin "3") (pinfunction "C_3") (pintype "passive"))
    )
    (net (code "96") (name "Net-(Q3-C)") (class "Default")
      (node (ref "J1") (pin "38") (pinfunction "38_38") (pintype "passive"))
      (node (ref "Q3") (pin "3") (pinfunction "C_3") (pintype "passive"))
    )
    (net (code "97") (name "Net-(Q4-C)") (class "Default")
      (node (ref "J1") (pin "40") (pinfunction "40_40") (pintype "passive"))
      (node (ref "Q4") (pin "3") (pinfunction "C_3") (pintype "passive"))
    )
    (net (code "98") (name "unconnected-(CN2-+5V-Pad18)") (class "Default")
      (node (ref "CN2") (pin "18") (pinfunction "+5V_18") (pintype "passive+no_connect"))
    )
    (net (code "99") (name "unconnected-(CN2-CEC-Pad13)") (class "Default")
      (node (ref "CN2") (pin "13") (pinfunction "CEC_13") (pintype "passive+no_connect"))
    )
    (net (code "100") (name "unconnected-(CN2-RES-Pad14)") (class "Default")
      (node (ref "CN2") (pin "14") (pinfunction "RES_14") (pintype "passive+no_connect"))
    )
    (net (code "101") (name "unconnected-(J1-Pad31)") (class "Default")
      (node (ref "J1") (pin "31") (pinfunction "31_31") (pintype "passive+no_connect"))
    )
    (net (code "102") (name "unconnected-(J2-Pad5)") (class "Default")
      (node (ref "J2") (pin "5") (pinfunction "5_5") (pintype "passive+no_connect"))
    )
    (net (code "103") (name "unconnected-(J2-Pad6)") (class "Default")
      (node (ref "J2") (pin "6") (pinfunction "6_6") (pintype "passive+no_connect"))
    )
    (net (code "104") (name "unconnected-(J2-Pad9)") (class "Default")
      (node (ref "J2") (pin "9") (pinfunction "9_9") (pintype "passive+no_connect"))
    )
    (net (code "105") (name "unconnected-(J2-Pad11)") (class "Default")
      (node (ref "J2") (pin "11") (pinfunction "11_11") (pintype "passive+no_connect"))
    )
    (net (code "106") (name "unconnected-(J2-Pad13)") (class "Default")
      (node (ref "J2") (pin "13") (pinfunction "13_13") (pintype "passive+no_connect"))
    )
    (net (code "107") (name "unconnected-(J2-Pad15)") (class "Default")
      (node (ref "J2") (pin "15") (pinfunction "15_15") (pintype "passive+no_connect"))
    )
    (net (code "108") (name "unconnected-(J2-Pad17)") (class "Default")
      (node (ref "J2") (pin "17") (pinfunction "17_17") (pintype "passive+no_connect"))
    )
    (net (code "109") (name "unconnected-(J2-Pad19)") (class "Default")
      (node (ref "J2") (pin "19") (pinfunction "19_19") (pintype "passive+no_connect"))
    )
    (net (code "110") (name "unconnected-(J2-Pad21)") (class "Default")
      (node (ref "J2") (pin "21") (pinfunction "21_21") (pintype "passive+no_connect"))
    )
    (net (code "111") (name "unconnected-(J2-Pad25)") (class "Default")
      (node (ref "J2") (pin "25") (pinfunction "25_25") (pintype "passive+no_connect"))
    )
    (net (code "112") (name "unconnected-(J2-Pad27)") (class "Default")
      (node (ref "J2") (pin "27") (pinfunction "27_27") (pintype "passive+no_connect"))
    )
    (net (code "113") (name "unconnected-(J2-Pad29)") (class "Default")
      (node (ref "J2") (pin "29") (pinfunction "29_29") (pintype "passive+no_connect"))
    )
  )
)
